# STM32H753_PINOUT.net
KiCad netlist of a schematic drawn in Altium Designer
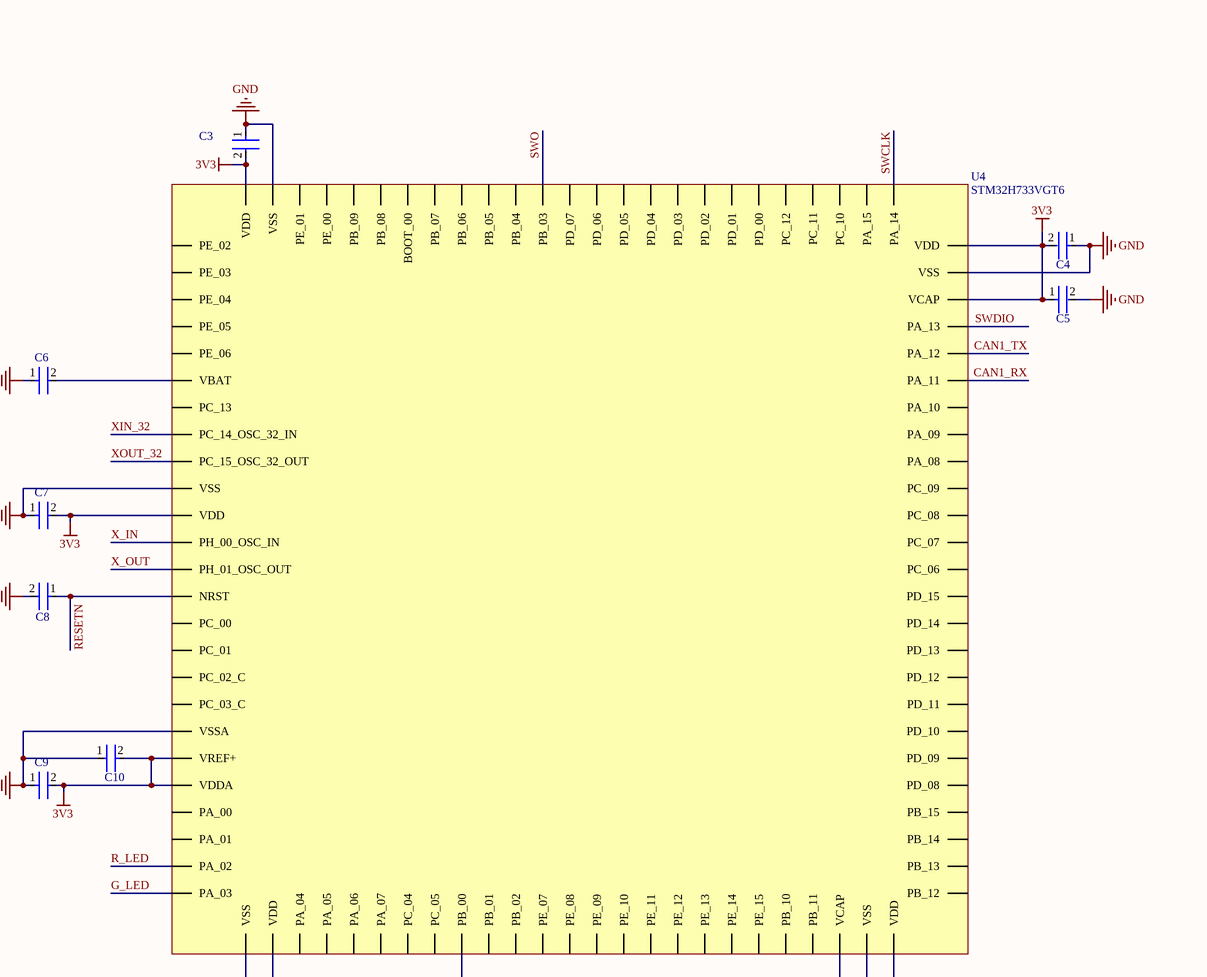
[diagram p0: STM32H753_PINOUT.SchDoc, top middle]
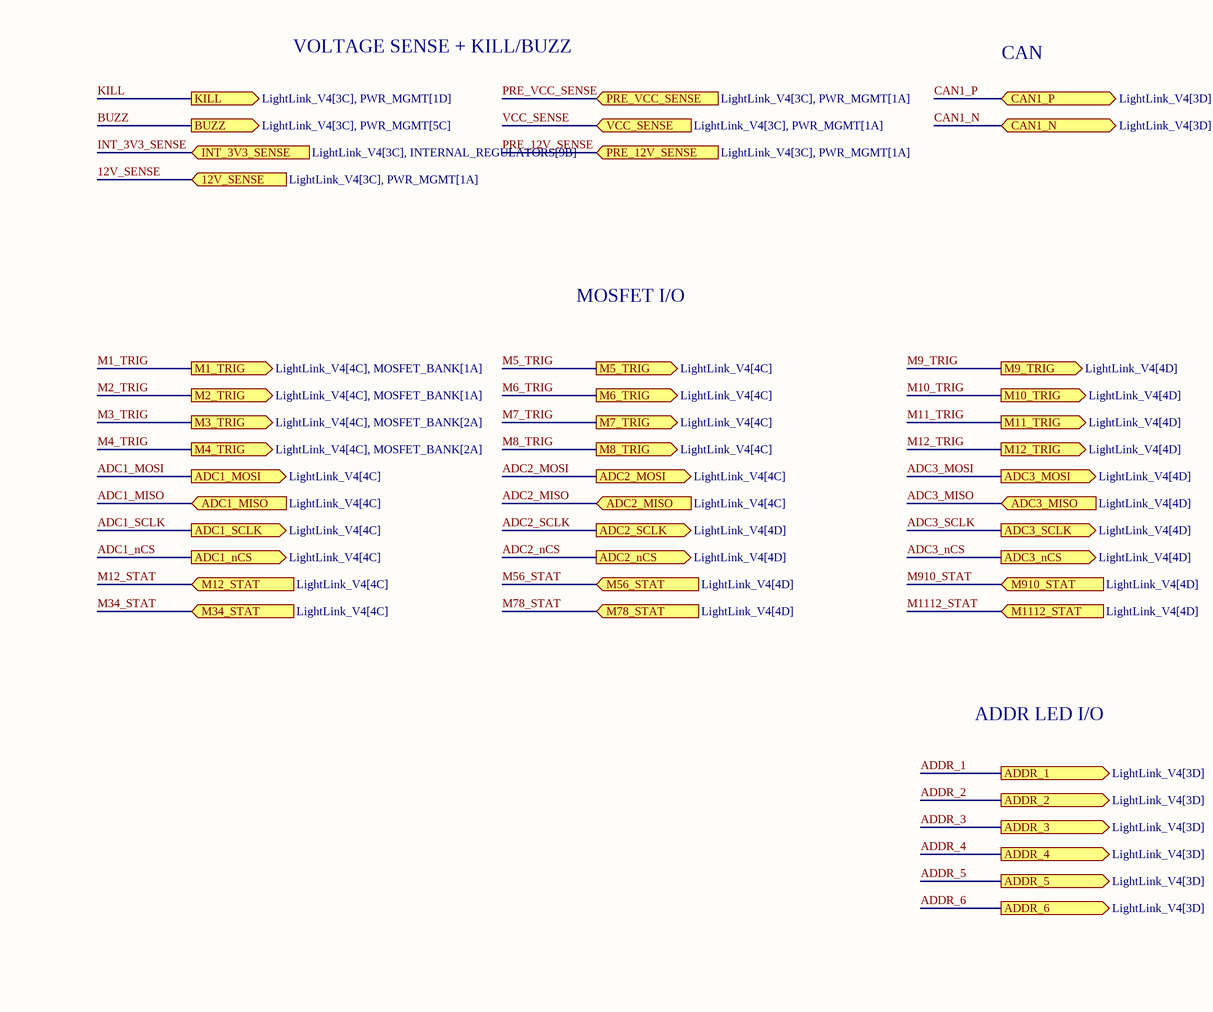
[diagram p1: STM32H753_PINOUT.SchDoc, top right]
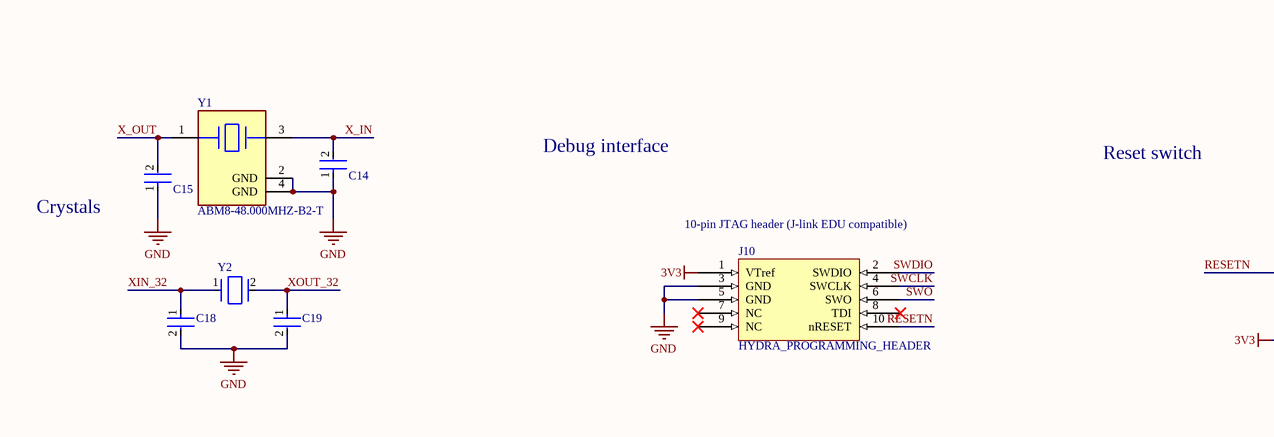
[diagram p2: STM32H753_PINOUT.SchDoc, bottom left]
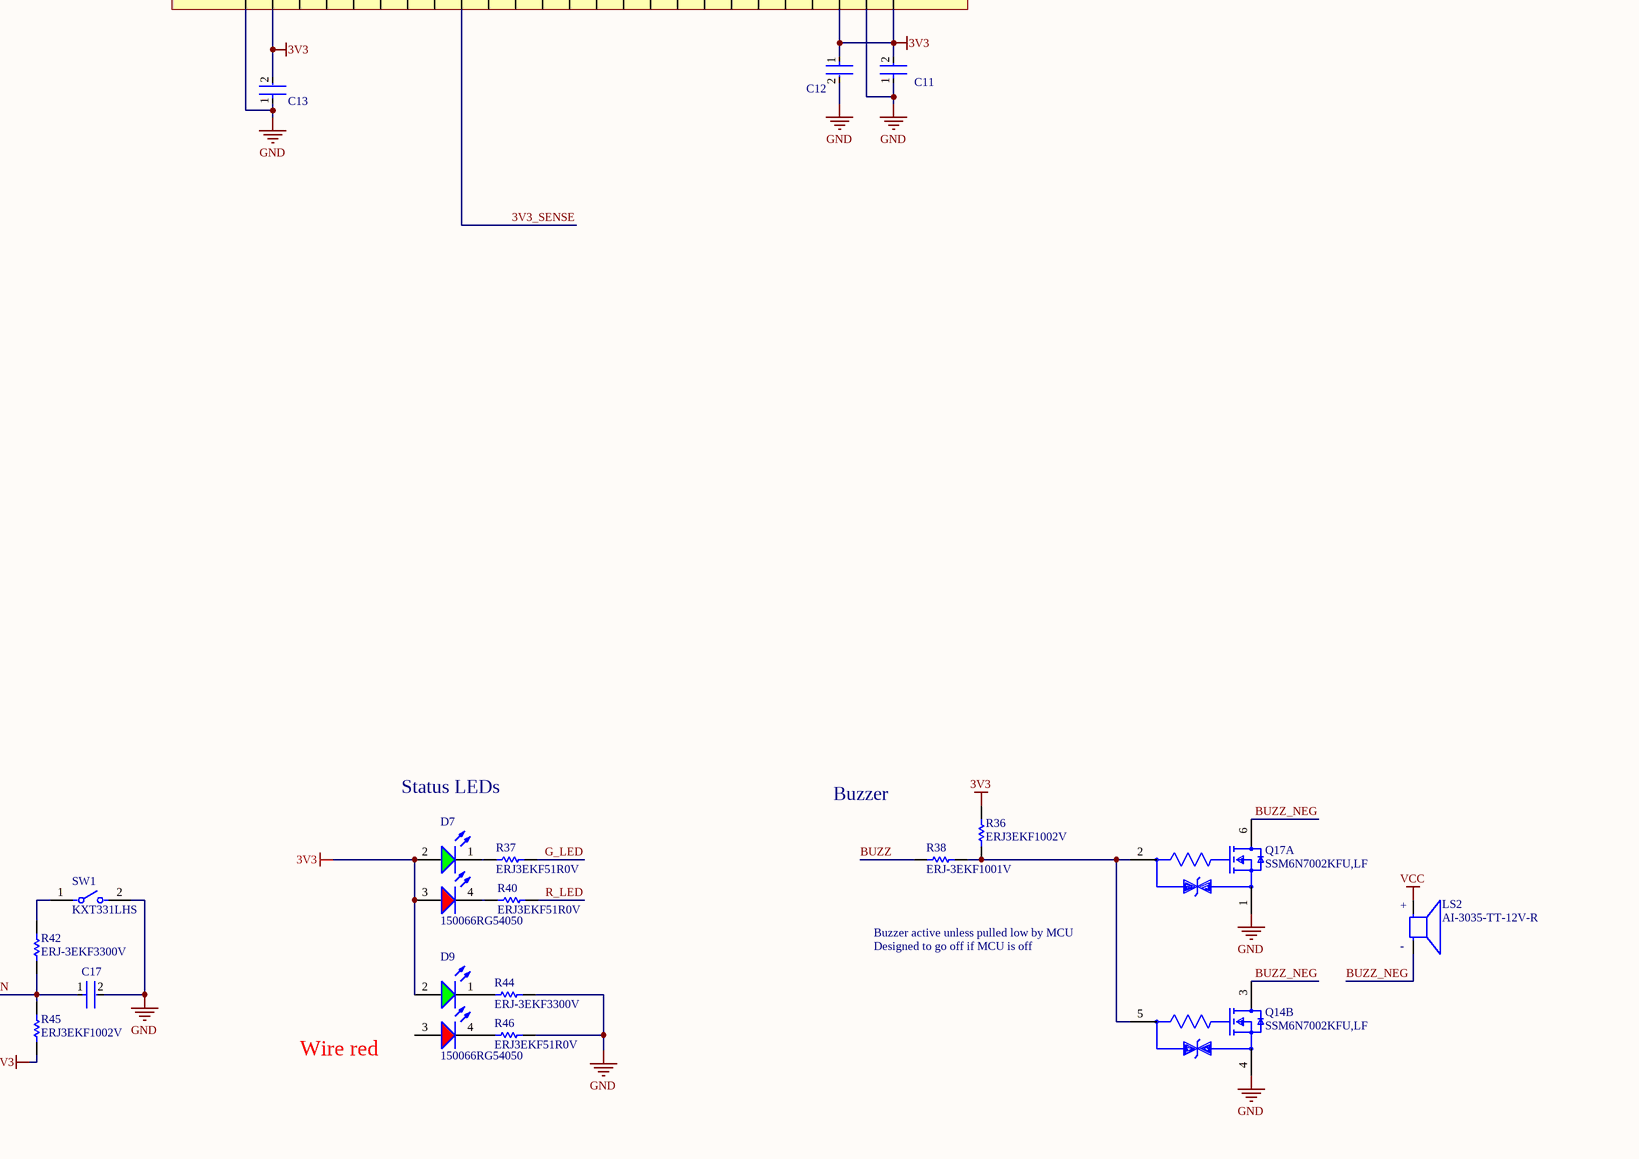
[diagram p3: STM32H753_PINOUT.SchDoc, bottom middle]
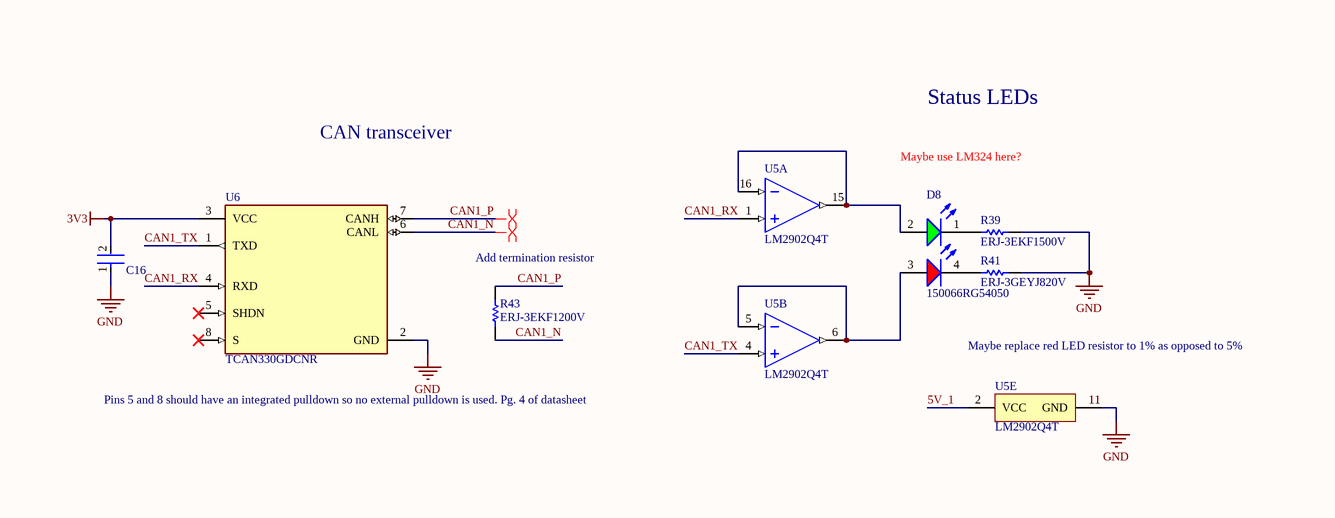
[diagram p4: STM32H753_PINOUT.SchDoc, bottom right]

(export (version "E")
  (design (tool "Eeschema 10.0.6"))
  (components
    (comp (ref "C3")
      (value "C0402C104K8PACTU")
      (footprint "FP-C0402-BB-MFG")
      (fields
        (field (name "MANUFACTURER") "Kemet")
        (field (name "TOLERANCE") "0.1")
        (field (name "OCTOPART") "https://octopart.com/c0402c104k8pactu-kemet-140039")
      )
      (libsource (lib "Altium Content Vault") (part "b4654b650e69147ec39a6b967a45e02"))
    )
    (comp (ref "C4")
      (value "C0402C104K8PACTU")
      (footprint "FP-C0402-BB-MFG")
      (fields
        (field (name "MANUFACTURER") "Kemet")
        (field (name "TOLERANCE") "0.1")
        (field (name "OCTOPART") "https://octopart.com/c0402c104k8pactu-kemet-140039")
      )
      (libsource (lib "Altium Content Vault") (part "b4654b650e69147ec39a6b967a45e02"))
    )
    (comp (ref "C5")
      (value "C1005X7S1A225K050BC")
      (footprint "FP-C1005-050-0_15-0_1-MFG")
      (description "CAP CER 2.2UF 10V X7S 0402")
      (fields (field (name "TOLERANCE") "10%"))
      (libsource (lib "Altium Content Vault") (part "b4654b650e69147ec39a6b967a45e02"))
    )
    (comp (ref "C6")
      (value "C0402C104K8PACTU")
      (footprint "FP-C0402-BB-MFG")
      (fields
        (field (name "MANUFACTURER") "Kemet")
        (field (name "TOLERANCE") "0.1")
        (field (name "OCTOPART") "https://octopart.com/c0402c104k8pactu-kemet-140039")
      )
      (libsource (lib "Altium Content Vault") (part "b4654b650e69147ec39a6b967a45e02"))
    )
    (comp (ref "C7")
      (value "C0402C104K8PACTU")
      (footprint "FP-C0402-BB-MFG")
      (fields
        (field (name "MANUFACTURER") "Kemet")
        (field (name "TOLERANCE") "0.1")
        (field (name "OCTOPART") "https://octopart.com/c0402c104k8pactu-kemet-140039")
      )
      (libsource (lib "Altium Content Vault") (part "b4654b650e69147ec39a6b967a45e02"))
    )
    (comp (ref "C8")
      (value "C0402C104K8PACTU")
      (footprint "FP-C0402-BB-MFG")
      (description "CAP CER 0.1UF 10V X5R 0402")
      (fields (field (name "MANUFACTURER") "Kemet") (field (name "TOLERANCE") "0.1"))
      (libsource (lib "Altium Content Vault") (part "b4654b650e69147ec39a6b967a45e02"))
    )
    (comp (ref "C9")
      (value "C0402C104K8PACTU")
      (footprint "FP-C0402-BB-MFG")
      (fields
        (field (name "MANUFACTURER") "Kemet")
        (field (name "TOLERANCE") "0.1")
        (field (name "OCTOPART") "https://octopart.com/c0402c104k8pactu-kemet-140039")
      )
      (libsource (lib "Altium Content Vault") (part "b4654b650e69147ec39a6b967a45e02"))
    )
    (comp (ref "C10")
      (value "GRM155R71C104KA88D")
      (footprint "FP-GRM15-MFG")
      (description "CAP CER 0.1UF 16V X7R 0402")
      (fields
        (field (name "TOLERANCE") "10%")
        (field (name "OCTOPART") "https://octopart.com/grm155r71c104ka88d-murata-196880")
      )
      (libsource (lib "Altium Content Vault") (part "236180d848d6139a670b325ea6854c9"))
    )
    (comp (ref "C11")
      (value "C0402C104K8PACTU")
      (footprint "FP-C0402-BB-MFG")
      (fields
        (field (name "MANUFACTURER") "Kemet")
        (field (name "TOLERANCE") "0.1")
        (field (name "OCTOPART") "https://octopart.com/c0402c104k8pactu-kemet-140039")
      )
      (libsource (lib "Altium Content Vault") (part "b4654b650e69147ec39a6b967a45e02"))
    )
    (comp (ref "C12")
      (value "C1005X7S1A225K050BC")
      (footprint "FP-C1005-050-0_15-0_1-MFG")
      (description "CAP CER 2.2UF 10V X7S 0402")
      (fields (field (name "TOLERANCE") "10%"))
      (libsource (lib "Altium Content Vault") (part "b4654b650e69147ec39a6b967a45e02"))
    )
    (comp (ref "C13")
      (value "C0402C104K8PACTU")
      (footprint "FP-C0402-BB-MFG")
      (fields
        (field (name "MANUFACTURER") "Kemet")
        (field (name "TOLERANCE") "0.1")
        (field (name "OCTOPART") "https://octopart.com/c0402c104k8pactu-kemet-140039")
      )
      (libsource (lib "Altium Content Vault") (part "b4654b650e69147ec39a6b967a45e02"))
    )
    (comp (ref "C14")
      (value "08051A6R8CAT2A")
      (footprint "FP-0805-L_2_01_0_2-W_1_25-MFG")
      (description "General Purpose Ceramic Capacitor, 0805, 6.8pF, 0.25pF, C0G, 30ppm/°C, 100V")
      (fields (field (name "VOLTAGE") "100V") (field (name "TOLERANCE") "5%"))
      (libsource (lib "Altium Content Vault") (part "02cd4be3c70576c341d710602a673aa"))
    )
    (comp (ref "C15")
      (value "08051A6R8CAT2A")
      (footprint "FP-0805-L_2_01_0_2-W_1_25-MFG")
      (description "General Purpose Ceramic Capacitor, 0805, 6.8pF, 0.25pF, C0G, 30ppm/°C, 100V")
      (fields (field (name "VOLTAGE") "100V") (field (name "TOLERANCE") "5%"))
      (libsource (lib "Altium Content Vault") (part "02cd4be3c70576c341d710602a673aa"))
    )
    (comp (ref "C16")
      (value "C0402C104K8PACTU")
      (footprint "FP-C0402-BB-MFG")
      (description "CAP CER 0.1UF 10V X5R 0402")
      (fields (field (name "MANUFACTURER") "Kemet") (field (name "TOLERANCE") "0.1"))
      (libsource (lib "Altium Content Vault") (part "b4654b650e69147ec39a6b967a45e02"))
    )
    (comp (ref "C17")
      (value "C0402C104K8PACTU")
      (footprint "FP-C0402-BB-MFG")
      (description "CAP CER 0.1UF 10V X5R 0402")
      (fields (field (name "MANUFACTURER") "Kemet") (field (name "TOLERANCE") "0.1"))
      (libsource (lib "Altium Content Vault") (part "b4654b650e69147ec39a6b967a45e02"))
    )
    (comp (ref "C18")
      (value "C0805C180J5GACTU")
      (footprint "FP-C0805C-DN-MFG")
      (description "CAP CER 18PF 50V C0G/NP0 0805")
      (fields
        (field (name "OCTOPART") "https://octopart.com/c0805c180j5gactu-kemet-144810")
        (field (name "TOLERANCE") "0.05")
      )
      (libsource (lib "Altium Content Vault") (part "b4654b650e69147ec39a6b967a45e02"))
    )
    (comp (ref "C19")
      (value "C0805C180J5GACTU")
      (footprint "FP-C0805C-DN-MFG")
      (description "CAP CER 18PF 50V C0G/NP0 0805")
      (fields
        (field (name "OCTOPART") "https://octopart.com/c0805c180j5gactu-kemet-144810")
        (field (name "TOLERANCE") "0.05")
      )
      (libsource (lib "Altium Content Vault") (part "b4654b650e69147ec39a6b967a45e02"))
    )
    (comp (ref "D7")
      (value "150066RG54050")
      (footprint "WL-SBCD_0606")
      (description "Led, Red/Grn, 180Mcd/230Mcd, 624Nm/525Nm Rohs Compliant: Yes")
      (libsource (lib "uORocketry Hardware") (part "WL-SBCD_0606_Red & Green"))
    )
    (comp (ref "D8")
      (value "150066RG54050")
      (footprint "WL-SBCD_0606")
      (description "Led, Red/Grn, 180Mcd/230Mcd, 624Nm/525Nm Rohs Compliant: Yes")
      (libsource (lib "uORocketry Hardware") (part "WL-SBCD_0606_Red & Green"))
    )
    (comp (ref "D9")
      (value "150066RG54050")
      (footprint "WL-SBCD_0606")
      (description "Led, Red/Grn, 180Mcd/230Mcd, 624Nm/525Nm Rohs Compliant: Yes")
      (libsource (lib "uORocketry Hardware") (part "WL-SBCD_0606_Red & Green"))
    )
    (comp (ref "J10")
      (value "HYDRA_PROGRAMMING_HEADER")
      (footprint "3220-10-0300-00-Footprint-1")
      (description "CONN HEADER SMD 10POS 1.27MM (specifically compatible with J-Link EDU cable) PN: 3220-10-0300-00")
      (libsource (lib "uORocketry Hardware") (part "3220-10-0300-00-Symbol-1"))
    )
    (comp (ref "LS2")
      (value "AI-3035-TT-12V-R")
      (footprint "AI-3035-TT-12V-R-Footprint-1")
      (description "Audio Indicator 12V 12mA 110dBA 3.5KHz Resonant Frequency Thru-Hole")
      (libsource (lib "uORocketry Hardware") (part "AI-3035-TT-12V-R"))
    )
    (comp (ref "Q14")
      (value "SSM6N7002KFU,LF")
      (footprint "FP-SSOP6-P-0_65A-MFG")
      (description "MOSFET 2N-CH 60V 0.3A")
      (libsource (lib "Altium Content Vault") (part "088aa6ac103fdeebe0d1c52ece6b7b9"))
    )
    (comp (ref "Q17")
      (value "SSM6N7002KFU,LF")
      (footprint "FP-SSOP6-P-0_65A-MFG")
      (description "MOSFET 2N-CH 60V 0.3A")
      (libsource (lib "Altium Content Vault") (part "088aa6ac103fdeebe0d1c52ece6b7b9"))
    )
    (comp (ref "R36")
      (value "ERJ3EKF1002V")
      (footprint "RESC1609X55X30LL15T15")
      (description "Chip Resistor, 10 KOhm, +/- 1%, 0.1 W, -55 to 155 degC, 0603 (1608 Metric), RoHS, Tape and Reel")
      (fields (field (name "TOLERANCE") "1%") (field (name "MANUFACTURER") "Panasonic"))
      (libsource (lib "Altium Content Vault") (part "RES-2"))
    )
    (comp (ref "R37")
      (value "ERJ3EKF51R0V")
      (footprint "RESC1608X55X30NL15T15")
      (fields (field (name "MANUFACTURER") "Panasonic"))
      (libsource (lib "Altium Content Vault") (part "RES"))
    )
    (comp (ref "R38")
      (value "ERJ-3EKF1001V")
      (footprint "RESC1608X55X30LL15T15")
      (fields (field (name "MANUFACTURER") "Panasonic"))
      (libsource (lib "Altium Content Vault") (part "RES"))
    )
    (comp (ref "R39")
      (value "ERJ-3EKF1500V")
      (footprint "RESC1608X55X30NL15T15")
      (fields (field (name "MANUFACTURER") "Panasonic"))
      (libsource (lib "Altium Content Vault") (part "RES"))
    )
    (comp (ref "R40")
      (value "ERJ3EKF51R0V")
      (footprint "RESC1608X55X30NL15T15")
      (fields (field (name "MANUFACTURER") "Panasonic"))
      (libsource (lib "Altium Content Vault") (part "RES"))
    )
    (comp (ref "R41")
      (value "ERJ-3GEYJ820V")
      (footprint "RESC1608X55X30NL15T15")
      (fields (field (name "MANUFACTURER") "Panasonic"))
      (libsource (lib "Altium Content Vault") (part "RES"))
    )
    (comp (ref "R42")
      (value "ERJ-3EKF3300V")
      (footprint "RESC1608X55X30LL15T15")
      (description "Chip Resistor, 330 Ohm, +/- 1%, 0.1 W, -55 to 155 degC, 0603 (1608 Metric), RoHS, Tape and Reel")
      (libsource (lib "Altium Content Vault") (part "RES-2"))
    )
    (comp (ref "R43")
      (value "ERJ-3EKF1200V")
      (footprint "RESC1609X55X30ML15T15")
      (description "Chip Resistor, 120 Ohm, +/- 1%, 0.1 W, -55 to 155 degC, 0603 (1608 Metric), RoHS, Tape and Reel")
      (fields (field (name "TOLERANCE") "1%") (field (name "MANUFACTURER") "Panasonic"))
      (libsource (lib "Altium Content Vault") (part "RES-2"))
    )
    (comp (ref "R44")
      (value "ERJ-3EKF3300V")
      (footprint "RESC1608X55X30LL15T15")
      (description "Chip Resistor, 330 Ohm, +/- 1%, 0.1 W, -55 to 155 degC, 0603 (1608 Metric), RoHS, Tape and Reel")
      (libsource (lib "Altium Content Vault") (part "RES-2"))
    )
    (comp (ref "R45")
      (value "ERJ3EKF1002V")
      (footprint "RESC1609X55X30LL15T15")
      (description "Chip Resistor, 10 KOhm, +/- 1%, 0.1 W, -55 to 155 degC, 0603 (1608 Metric), RoHS, Tape and Reel")
      (fields (field (name "TOLERANCE") "1%") (field (name "MANUFACTURER") "Panasonic"))
      (libsource (lib "Altium Content Vault") (part "RES-2"))
    )
    (comp (ref "R46")
      (value "ERJ3EKF51R0V")
      (footprint "RESC1608X55X30NL15T15")
      (fields (field (name "MANUFACTURER") "Panasonic"))
      (libsource (lib "Altium Content Vault") (part "RES"))
    )
    (comp (ref "SW1")
      (value "KXT331LHS")
      (footprint "FP-KXT331LHS-MFG")
      (description "SWITCH TACTILE SPST-NO 0.02A 15V")
      (libsource (lib "Altium Content Vault") (part "bb27bde45df87f1f469753f287ef5ae"))
    )
    (comp (ref "U4")
      (value "STM32H733VGT6")
      (footprint "STM32H733VGT6-Footprint-1")
      (description "MCU 32-bit ARM Cortex M7 RISC 1MB Flash 1.8V/2.5V/3.3V 100-Pin LQFP Tray")
      (libsource (lib "uORocketry Hardware") (part "STM32H733VGT6"))
    )
    (comp (ref "U5")
      (value "LM2902Q4T")
      (footprint "LM2902Q4T-Footprint-1")
      (description "LM2902 Series 30 V 1.3 MHz Low-Power Quad Operational Amplifier - QFN-16 (3x3)")
      (libsource (lib "uORocketry Hardware") (part "LM2902Q4T"))
    )
    (comp (ref "U6")
      (value "TCAN330GDCNR")
      (footprint "FP-DCN0008A-MFG")
      (description "IC TRANSCEIVER 1/1 SOT23-8")
      (libsource (lib "Altium Content Vault") (part "22681b49c22ad38c6a4e12e04c36c7a"))
    )
    (comp (ref "Y1")
      (value "ABM8-48.000MHZ-B2-T")
      (footprint "FP-ABM8-MFG")
      (description "Crystal 48MHz ±20ppm 18pF SMD-4 3.2mm x 2.5mm")
      (fields (field (name "TOLERANCE") "20ppm"))
      (libsource (lib "Altium Content Vault") (part "dfdb7f9a12507849fb681da9a70121c"))
    )
    (comp (ref "Y2")
      (value "ECS-.327-12.5-1210-TR")
      (footprint "FP-ECX-1210-MFG")
      (description "CRYSTAL 32.7680KHZ 12.5PF SMD")
      (fields
        (field (name "OCTOPART") "https://octopart.com/ecs-.327-12.5-1210-tr-ecs+international-81221340")
        (field (name "TOLERANCE") "20ppm")
      )
      (libsource (lib "Altium Content Vault") (part "99724985039315a44fd0d1401b84e49"))
    )
  )
  (nets
    (net (code "1") (name "/3V3_SENSE") (class "Default")
      (node (ref "U4") (pin "34") (pinfunction "PB_00_34") (pintype "passive"))
    )
    (net (code "2") (name "/5V_1") (class "Default")
      (node (ref "U5") (pin "2") (pinfunction "VCC_2") (pintype "power_in"))
    )
    (net (code "22") (name "/BUZZ") (class "Default")
      (node (ref "R38") (pin "1") (pinfunction "1_1") (pintype "passive"))
    )
    (net (code "23") (name "/BUZZ_NEG") (class "Default")
      (node (ref "LS2") (pin "N") (pinfunction "N_N") (pintype "passive"))
      (node (ref "Q14") (pin "3") (pinfunction "Drain2_3") (pintype "passive"))
      (node (ref "Q17") (pin "6") (pinfunction "Drain1_6") (pintype "passive"))
    )
    (net (code "24") (name "/CAN1_N") (class "Default")
      (node (ref "R43") (pin "1") (pinfunction "1_1") (pintype "passive"))
      (node (ref "U6") (pin "6") (pinfunction "CANL_6") (pintype "bidirectional"))
    )
    (net (code "25") (name "/CAN1_P") (class "Default")
      (node (ref "R43") (pin "2") (pinfunction "2_2") (pintype "passive"))
      (node (ref "U6") (pin "7") (pinfunction "CANH_7") (pintype "bidirectional"))
    )
    (net (code "26") (name "/CAN1_RX") (class "Default")
      (node (ref "U4") (pin "70") (pinfunction "PA_11_70") (pintype "passive"))
      (node (ref "U5") (pin "1") (pinfunction "1IN+_1") (pintype "input"))
      (node (ref "U6") (pin "4") (pinfunction "RXD_4") (pintype "input"))
    )
    (net (code "27") (name "/CAN1_TX") (class "Default")
      (node (ref "U4") (pin "71") (pinfunction "PA_12_71") (pintype "passive"))
      (node (ref "U5") (pin "4") (pinfunction "2IN+_4") (pintype "input"))
      (node (ref "U6") (pin "1") (pinfunction "TXD_1") (pintype "output"))
    )
    (net (code "28") (name "/G_LED") (class "Default")
      (node (ref "R37") (pin "2") (pinfunction "2_2") (pintype "passive"))
      (node (ref "U4") (pin "25") (pinfunction "PA_03_25") (pintype "passive"))
    )
    (net (code "51") (name "/RESETN") (class "Default")
      (node (ref "C17") (pin "1") (pinfunction "1_1") (pintype "passive"))
      (node (ref "C8") (pin "1") (pinfunction "1_1") (pintype "passive"))
      (node (ref "J10") (pin "10") (pinfunction "nRESET_10") (pintype "input"))
      (node (ref "R42") (pin "1") (pinfunction "1_1") (pintype "passive"))
      (node (ref "R45") (pin "2") (pinfunction "2_2") (pintype "passive"))
      (node (ref "U4") (pin "14") (pinfunction "NRST_14") (pintype "passive"))
    )
    (net (code "52") (name "/R_LED") (class "Default")
      (node (ref "R40") (pin "2") (pinfunction "2_2") (pintype "passive"))
      (node (ref "U4") (pin "24") (pinfunction "PA_02_24") (pintype "passive"))
    )
    (net (code "53") (name "/SWCLK") (class "Default")
      (node (ref "J10") (pin "4") (pinfunction "SWCLK_4") (pintype "input"))
      (node (ref "U4") (pin "76") (pinfunction "PA_14_76") (pintype "passive"))
    )
    (net (code "54") (name "/SWDIO") (class "Default")
      (node (ref "J10") (pin "2") (pinfunction "SWDIO_2") (pintype "input"))
      (node (ref "U4") (pin "72") (pinfunction "PA_13_72") (pintype "passive"))
    )
    (net (code "55") (name "/SWO") (class "Default")
      (node (ref "J10") (pin "6") (pinfunction "SWO_6") (pintype "input"))
      (node (ref "U4") (pin "89") (pinfunction "PB_03_89") (pintype "passive"))
    )
    (net (code "57") (name "/XIN_32") (class "Default")
      (node (ref "C18") (pin "1") (pinfunction "1_1") (pintype "passive"))
      (node (ref "U4") (pin "8") (pinfunction "PC_14_OSC_32_IN_8") (pintype "passive"))
      (node (ref "Y2") (pin "1") (pinfunction "In/Out_1") (pintype "passive"))
    )
    (net (code "58") (name "/XOUT_32") (class "Default")
      (node (ref "C19") (pin "1") (pinfunction "1_1") (pintype "passive"))
      (node (ref "U4") (pin "9") (pinfunction "PC_15_OSC_32_OUT_9") (pintype "passive"))
      (node (ref "Y2") (pin "2") (pinfunction "Out/In_2") (pintype "passive"))
    )
    (net (code "59") (name "/X_IN") (class "Default")
      (node (ref "C14") (pin "2") (pinfunction "2_2") (pintype "passive"))
      (node (ref "U4") (pin "12") (pinfunction "PH_00_OSC_IN_12") (pintype "passive"))
      (node (ref "Y1") (pin "3") (pinfunction "3_3") (pintype "passive"))
    )
    (net (code "60") (name "/X_OUT") (class "Default")
      (node (ref "C15") (pin "2") (pinfunction "2_2") (pintype "passive"))
      (node (ref "U4") (pin "13") (pinfunction "PH_01_OSC_OUT_13") (pintype "passive"))
      (node (ref "Y1") (pin "1") (pinfunction "1_1") (pintype "passive"))
    )
    (net (code "61") (name "3V3") (class "Default")
      (node (ref "C10") (pin "2") (pinfunction "2_2") (pintype "passive"))
      (node (ref "C11") (pin "2") (pinfunction "2_2") (pintype "passive"))
      (node (ref "C12") (pin "1") (pinfunction "1_1") (pintype "passive"))
      (node (ref "C13") (pin "2") (pinfunction "2_2") (pintype "passive"))
      (node (ref "C16") (pin "2") (pinfunction "2_2") (pintype "passive"))
      (node (ref "C3") (pin "2") (pinfunction "2_2") (pintype "passive"))
      (node (ref "C4") (pin "2") (pinfunction "2_2") (pintype "passive"))
      (node (ref "C5") (pin "1") (pinfunction "1_1") (pintype "passive"))
      (node (ref "C7") (pin "2") (pinfunction "2_2") (pintype "passive"))
      (node (ref "C9") (pin "2") (pinfunction "2_2") (pintype "passive"))
      (node (ref "D7") (pin "2") (pinfunction "A_2") (pintype "passive"))
      (node (ref "D7") (pin "3") (pinfunction "A_3") (pintype "passive"))
      (node (ref "D9") (pin "2") (pinfunction "A_2") (pintype "passive"))
      (node (ref "J10") (pin "1") (pinfunction "VTref_1") (pintype "input"))
      (node (ref "R36") (pin "2") (pinfunction "2_2") (pintype "passive"))
      (node (ref "R45") (pin "1") (pinfunction "1_1") (pintype "passive"))
      (node (ref "U4") (pin "100") (pinfunction "VDD_100") (pintype "passive"))
      (node (ref "U4") (pin "11") (pinfunction "VDD_11") (pintype "passive"))
      (node (ref "U4") (pin "20") (pinfunction "VREF+_20") (pintype "passive"))
      (node (ref "U4") (pin "21") (pinfunction "VDDA_21") (pintype "passive"))
      (node (ref "U4") (pin "27") (pinfunction "VDD_27") (pintype "passive"))
      (node (ref "U4") (pin "48") (pinfunction "VCAP_48") (pintype "passive"))
      (node (ref "U4") (pin "50") (pinfunction "VDD_50") (pintype "passive"))
      (node (ref "U4") (pin "73") (pinfunction "VCAP_73") (pintype "passive"))
      (node (ref "U4") (pin "75") (pinfunction "VDD_75") (pintype "passive"))
      (node (ref "U6") (pin "3") (pinfunction "VCC_3") (pintype "power_in"))
    )
    (net (code "62") (name "GND") (class "Default")
      (node (ref "C10") (pin "1") (pinfunction "1_1") (pintype "passive"))
      (node (ref "C11") (pin "1") (pinfunction "1_1") (pintype "passive"))
      (node (ref "C12") (pin "2") (pinfunction "2_2") (pintype "passive"))
      (node (ref "C13") (pin "1") (pinfunction "1_1") (pintype "passive"))
      (node (ref "C14") (pin "1") (pinfunction "1_1") (pintype "passive"))
      (node (ref "C15") (pin "1") (pinfunction "1_1") (pintype "passive"))
      (node (ref "C16") (pin "1") (pinfunction "1_1") (pintype "passive"))
      (node (ref "C17") (pin "2") (pinfunction "2_2") (pintype "passive"))
      (node (ref "C18") (pin "2") (pinfunction "2_2") (pintype "passive"))
      (node (ref "C19") (pin "2") (pinfunction "2_2") (pintype "passive"))
      (node (ref "C3") (pin "1") (pinfunction "1_1") (pintype "passive"))
      (node (ref "C4") (pin "1") (pinfunction "1_1") (pintype "passive"))
      (node (ref "C5") (pin "2") (pinfunction "2_2") (pintype "passive"))
      (node (ref "C6") (pin "1") (pinfunction "1_1") (pintype "passive"))
      (node (ref "C7") (pin "1") (pinfunction "1_1") (pintype "passive"))
      (node (ref "C8") (pin "2") (pinfunction "2_2") (pintype "passive"))
      (node (ref "C9") (pin "1") (pinfunction "1_1") (pintype "passive"))
      (node (ref "J10") (pin "3") (pinfunction "GND_3") (pintype "input"))
      (node (ref "J10") (pin "5") (pinfunction "GND_5") (pintype "input"))
      (node (ref "Q14") (pin "4") (pinfunction "Source2_4") (pintype "passive"))
      (node (ref "Q17") (pin "1") (pinfunction "Source1_1") (pintype "passive"))
      (node (ref "R39") (pin "2") (pinfunction "2_2") (pintype "passive"))
      (node (ref "R41") (pin "2") (pinfunction "2_2") (pintype "passive"))
      (node (ref "R44") (pin "2") (pinfunction "2_2") (pintype "passive"))
      (node (ref "R46") (pin "2") (pinfunction "2_2") (pintype "passive"))
      (node (ref "SW1") (pin "2") (pinfunction "2_2") (pintype "passive"))
      (node (ref "U4") (pin "10") (pinfunction "VSS_10") (pintype "passive"))
      (node (ref "U4") (pin "19") (pinfunction "VSSA_19") (pintype "passive"))
      (node (ref "U4") (pin "26") (pinfunction "VSS_26") (pintype "passive"))
      (node (ref "U4") (pin "49") (pinfunction "VSS_49") (pintype "passive"))
      (node (ref "U4") (pin "74") (pinfunction "VSS_74") (pintype "passive"))
      (node (ref "U4") (pin "99") (pinfunction "VSS_99") (pintype "passive"))
      (node (ref "U5") (pin "11") (pinfunction "GND_11") (pintype "power_in"))
      (node (ref "U6") (pin "2") (pinfunction "GND_2") (pintype "power_in"))
      (node (ref "Y1") (pin "2") (pinfunction "GND_2") (pintype "power_in"))
      (node (ref "Y1") (pin "4") (pinfunction "GND_4") (pintype "power_in"))
    )
    (net (code "63") (name "Net-(D7-K-Pad1)") (class "Default")
      (node (ref "D7") (pin "1") (pinfunction "K_1") (pintype "passive"))
      (node (ref "R37") (pin "1") (pinfunction "1_1") (pintype "passive"))
    )
    (net (code "64") (name "Net-(D7-K-Pad4)") (class "Default")
      (node (ref "D7") (pin "4") (pinfunction "K_4") (pintype "passive"))
      (node (ref "R40") (pin "1") (pinfunction "1_1") (pintype "passive"))
    )
    (net (code "65") (name "Net-(D8-K-Pad1)") (class "Default")
      (node (ref "D8") (pin "1") (pinfunction "K_1") (pintype "passive"))
      (node (ref "R39") (pin "1") (pinfunction "1_1") (pintype "passive"))
    )
    (net (code "66") (name "Net-(D8-K-Pad4)") (class "Default")
      (node (ref "D8") (pin "4") (pinfunction "K_4") (pintype "passive"))
      (node (ref "R41") (pin "1") (pinfunction "1_1") (pintype "passive"))
    )
    (net (code "67") (name "Net-(D9-K-Pad1)") (class "Default")
      (node (ref "D9") (pin "1") (pinfunction "K_1") (pintype "passive"))
      (node (ref "R44") (pin "1") (pinfunction "1_1") (pintype "passive"))
    )
    (net (code "68") (name "Net-(D9-K-Pad4)") (class "Default")
      (node (ref "D9") (pin "4") (pinfunction "K_4") (pintype "passive"))
      (node (ref "R46") (pin "1") (pinfunction "1_1") (pintype "passive"))
    )
    (net (code "69") (name "Net-(Q14B-Gate2)") (class "Default")
      (node (ref "Q14") (pin "5") (pinfunction "Gate2_5") (pintype "passive"))
      (node (ref "Q17") (pin "2") (pinfunction "Gate1_2") (pintype "passive"))
      (node (ref "R36") (pin "1") (pinfunction "1_1") (pintype "passive"))
      (node (ref "R38") (pin "2") (pinfunction "2_2") (pintype "passive"))
    )
    (net (code "70") (name "Net-(R42-Pad2)") (class "Default")
      (node (ref "R42") (pin "2") (pinfunction "2_2") (pintype "passive"))
      (node (ref "SW1") (pin "1") (pinfunction "1_1") (pintype "passive"))
    )
    (net (code "71") (name "Net-(U4-VBAT)") (class "Default")
      (node (ref "C6") (pin "2") (pinfunction "2_2") (pintype "passive"))
      (node (ref "U4") (pin "6") (pinfunction "VBAT_6") (pintype "passive"))
    )
    (net (code "72") (name "Net-(U5A-1IN-)") (class "Default")
      (node (ref "D8") (pin "2") (pinfunction "A_2") (pintype "passive"))
      (node (ref "U5") (pin "15") (pinfunction "1OUT_15") (pintype "output"))
      (node (ref "U5") (pin "16") (pinfunction "1IN-_16") (pintype "input"))
    )
    (net (code "73") (name "Net-(U5B-2IN-)") (class "Default")
      (node (ref "D8") (pin "3") (pinfunction "A_3") (pintype "passive"))
      (node (ref "U5") (pin "5") (pinfunction "2IN-_5") (pintype "input"))
      (node (ref "U5") (pin "6") (pinfunction "2OUT_6") (pintype "output"))
    )
    (net (code "74") (name "VCC") (class "Default")
      (node (ref "LS2") (pin "P") (pinfunction "P_P") (pintype "passive"))
    )
    (net (code "75") (name "unconnected-(D9-A-Pad3)") (class "Default")
      (node (ref "D9") (pin "3") (pinfunction "A_3") (pintype "passive"))
    )
    (net (code "76") (name "unconnected-(J10-NC-Pad7)") (class "Default")
      (node (ref "J10") (pin "7") (pinfunction "NC_7") (pintype "input+no_connect"))
    )
    (net (code "77") (name "unconnected-(J10-NC-Pad9)") (class "Default")
      (node (ref "J10") (pin "9") (pinfunction "NC_9") (pintype "input+no_connect"))
    )
    (net (code "78") (name "unconnected-(J10-TDI-Pad8)") (class "Default")
      (node (ref "J10") (pin "8") (pinfunction "TDI_8") (pintype "input+no_connect"))
    )
    (net (code "79") (name "unconnected-(U4-BOOT_00-Pad94)") (class "Default")
      (node (ref "U4") (pin "94") (pinfunction "BOOT_00_94") (pintype "passive"))
    )
    (net (code "80") (name "unconnected-(U4-PA_00-Pad22)") (class "Default")
      (node (ref "U4") (pin "22") (pinfunction "PA_00_22") (pintype "passive"))
    )
    (net (code "81") (name "unconnected-(U4-PA_01-Pad23)") (class "Default")
      (node (ref "U4") (pin "23") (pinfunction "PA_01_23") (pintype "passive"))
    )
    (net (code "82") (name "unconnected-(U4-PA_04-Pad28)") (class "Default")
      (node (ref "U4") (pin "28") (pinfunction "PA_04_28") (pintype "passive"))
    )
    (net (code "83") (name "unconnected-(U4-PA_05-Pad29)") (class "Default")
      (node (ref "U4") (pin "29") (pinfunction "PA_05_29") (pintype "passive"))
    )
    (net (code "84") (name "unconnected-(U4-PA_06-Pad30)") (class "Default")
      (node (ref "U4") (pin "30") (pinfunction "PA_06_30") (pintype "passive"))
    )
    (net (code "85") (name "unconnected-(U4-PA_07-Pad31)") (class "Default")
      (node (ref "U4") (pin "31") (pinfunction "PA_07_31") (pintype "passive"))
    )
    (net (code "86") (name "unconnected-(U4-PA_08-Pad67)") (class "Default")
      (node (ref "U4") (pin "67") (pinfunction "PA_08_67") (pintype "passive"))
    )
    (net (code "87") (name "unconnected-(U4-PA_09-Pad68)") (class "Default")
      (node (ref "U4") (pin "68") (pinfunction "PA_09_68") (pintype "passive"))
    )
    (net (code "88") (name "unconnected-(U4-PA_10-Pad69)") (class "Default")
      (node (ref "U4") (pin "69") (pinfunction "PA_10_69") (pintype "passive"))
    )
    (net (code "89") (name "unconnected-(U4-PA_15-Pad77)") (class "Default")
      (node (ref "U4") (pin "77") (pinfunction "PA_15_77") (pintype "passive"))
    )
    (net (code "90") (name "unconnected-(U4-PB_01-Pad35)") (class "Default")
      (node (ref "U4") (pin "35") (pinfunction "PB_01_35") (pintype "passive"))
    )
    (net (code "91") (name "unconnected-(U4-PB_02-Pad36)") (class "Default")
      (node (ref "U4") (pin "36") (pinfunction "PB_02_36") (pintype "passive"))
    )
    (net (code "92") (name "unconnected-(U4-PB_04-Pad90)") (class "Default")
      (node (ref "U4") (pin "90") (pinfunction "PB_04_90") (pintype "passive"))
    )
    (net (code "93") (name "unconnected-(U4-PB_05-Pad91)") (class "Default")
      (node (ref "U4") (pin "91") (pinfunction "PB_05_91") (pintype "passive"))
    )
    (net (code "94") (name "unconnected-(U4-PB_06-Pad92)") (class "Default")
      (node (ref "U4") (pin "92") (pinfunction "PB_06_92") (pintype "passive"))
    )
    (net (code "95") (name "unconnected-(U4-PB_07-Pad93)") (class "Default")
      (node (ref "U4") (pin "93") (pinfunction "PB_07_93") (pintype "passive"))
    )
    (net (code "96") (name "unconnected-(U4-PB_08-Pad95)") (class "Default")
      (node (ref "U4") (pin "95") (pinfunction "PB_08_95") (pintype "passive"))
    )
    (net (code "97") (name "unconnected-(U4-PB_09-Pad96)") (class "Default")
      (node (ref "U4") (pin "96") (pinfunction "PB_09_96") (pintype "passive"))
    )
    (net (code "98") (name "unconnected-(U4-PB_10-Pad46)") (class "Default")
      (node (ref "U4") (pin "46") (pinfunction "PB_10_46") (pintype "passive"))
    )
    (net (code "99") (name "unconnected-(U4-PB_11-Pad47)") (class "Default")
      (node (ref "U4") (pin "47") (pinfunction "PB_11_47") (pintype "passive"))
    )
    (net (code "100") (name "unconnected-(U4-PB_12-Pad51)") (class "Default")
      (node (ref "U4") (pin "51") (pinfunction "PB_12_51") (pintype "passive"))
    )
    (net (code "101") (name "unconnected-(U4-PB_13-Pad52)") (class "Default")
      (node (ref "U4") (pin "52") (pinfunction "PB_13_52") (pintype "passive"))
    )
    (net (code "102") (name "unconnected-(U4-PB_14-Pad53)") (class "Default")
      (node (ref "U4") (pin "53") (pinfunction "PB_14_53") (pintype "passive"))
    )
    (net (code "103") (name "unconnected-(U4-PB_15-Pad54)") (class "Default")
      (node (ref "U4") (pin "54") (pinfunction "PB_15_54") (pintype "passive"))
    )
    (net (code "104") (name "unconnected-(U4-PC_00-Pad15)") (class "Default")
      (node (ref "U4") (pin "15") (pinfunction "PC_00_15") (pintype "passive"))
    )
    (net (code "105") (name "unconnected-(U4-PC_01-Pad16)") (class "Default")
      (node (ref "U4") (pin "16") (pinfunction "PC_01_16") (pintype "passive"))
    )
    (net (code "106") (name "unconnected-(U4-PC_02_C-Pad17)") (class "Default")
      (node (ref "U4") (pin "17") (pinfunction "PC_02_C_17") (pintype "passive"))
    )
    (net (code "107") (name "unconnected-(U4-PC_03_C-Pad18)") (class "Default")
      (node (ref "U4") (pin "18") (pinfunction "PC_03_C_18") (pintype "passive"))
    )
    (net (code "108") (name "unconnected-(U4-PC_04-Pad32)") (class "Default")
      (node (ref "U4") (pin "32") (pinfunction "PC_04_32") (pintype "passive"))
    )
    (net (code "109") (name "unconnected-(U4-PC_05-Pad33)") (class "Default")
      (node (ref "U4") (pin "33") (pinfunction "PC_05_33") (pintype "passive"))
    )
    (net (code "110") (name "unconnected-(U4-PC_06-Pad63)") (class "Default")
      (node (ref "U4") (pin "63") (pinfunction "PC_06_63") (pintype "passive"))
    )
    (net (code "111") (name "unconnected-(U4-PC_07-Pad64)") (class "Default")
      (node (ref "U4") (pin "64") (pinfunction "PC_07_64") (pintype "passive"))
    )
    (net (code "112") (name "unconnected-(U4-PC_08-Pad65)") (class "Default")
      (node (ref "U4") (pin "65") (pinfunction "PC_08_65") (pintype "passive"))
    )
    (net (code "113") (name "unconnected-(U4-PC_09-Pad66)") (class "Default")
      (node (ref "U4") (pin "66") (pinfunction "PC_09_66") (pintype "passive"))
    )
    (net (code "114") (name "unconnected-(U4-PC_10-Pad78)") (class "Default")
      (node (ref "U4") (pin "78") (pinfunction "PC_10_78") (pintype "passive"))
    )
    (net (code "115") (name "unconnected-(U4-PC_11-Pad79)") (class "Default")
      (node (ref "U4") (pin "79") (pinfunction "PC_11_79") (pintype "passive"))
    )
    (net (code "116") (name "unconnected-(U4-PC_12-Pad80)") (class "Default")
      (node (ref "U4") (pin "80") (pinfunction "PC_12_80") (pintype "passive"))
    )
    (net (code "117") (name "unconnected-(U4-PC_13-Pad7)") (class "Default")
      (node (ref "U4") (pin "7") (pinfunction "PC_13_7") (pintype "passive"))
    )
    (net (code "118") (name "unconnected-(U4-PD_00-Pad81)") (class "Default")
      (node (ref "U4") (pin "81") (pinfunction "PD_00_81") (pintype "passive"))
    )
    (net (code "119") (name "unconnected-(U4-PD_01-Pad82)") (class "Default")
      (node (ref "U4") (pin "82") (pinfunction "PD_01_82") (pintype "passive"))
    )
    (net (code "120") (name "unconnected-(U4-PD_02-Pad83)") (class "Default")
      (node (ref "U4") (pin "83") (pinfunction "PD_02_83") (pintype "passive"))
    )
    (net (code "121") (name "unconnected-(U4-PD_03-Pad84)") (class "Default")
      (node (ref "U4") (pin "84") (pinfunction "PD_03_84") (pintype "passive"))
    )
    (net (code "122") (name "unconnected-(U4-PD_04-Pad85)") (class "Default")
      (node (ref "U4") (pin "85") (pinfunction "PD_04_85") (pintype "passive"))
    )
    (net (code "123") (name "unconnected-(U4-PD_05-Pad86)") (class "Default")
      (node (ref "U4") (pin "86") (pinfunction "PD_05_86") (pintype "passive"))
    )
    (net (code "124") (name "unconnected-(U4-PD_06-Pad87)") (class "Default")
      (node (ref "U4") (pin "87") (pinfunction "PD_06_87") (pintype "passive"))
    )
    (net (code "125") (name "unconnected-(U4-PD_07-Pad88)") (class "Default")
      (node (ref "U4") (pin "88") (pinfunction "PD_07_88") (pintype "passive"))
    )
    (net (code "126") (name "unconnected-(U4-PD_08-Pad55)") (class "Default")
      (node (ref "U4") (pin "55") (pinfunction "PD_08_55") (pintype "passive"))
    )
    (net (code "127") (name "unconnected-(U4-PD_09-Pad56)") (class "Default")
      (node (ref "U4") (pin "56") (pinfunction "PD_09_56") (pintype "passive"))
    )
    (net (code "128") (name "unconnected-(U4-PD_10-Pad57)") (class "Default")
      (node (ref "U4") (pin "57") (pinfunction "PD_10_57") (pintype "passive"))
    )
    (net (code "129") (name "unconnected-(U4-PD_11-Pad58)") (class "Default")
      (node (ref "U4") (pin "58") (pinfunction "PD_11_58") (pintype "passive"))
    )
    (net (code "130") (name "unconnected-(U4-PD_12-Pad59)") (class "Default")
      (node (ref "U4") (pin "59") (pinfunction "PD_12_59") (pintype "passive"))
    )
    (net (code "131") (name "unconnected-(U4-PD_13-Pad60)") (class "Default")
      (node (ref "U4") (pin "60") (pinfunction "PD_13_60") (pintype "passive"))
    )
    (net (code "132") (name "unconnected-(U4-PD_14-Pad61)") (class "Default")
      (node (ref "U4") (pin "61") (pinfunction "PD_14_61") (pintype "passive"))
    )
    (net (code "133") (name "unconnected-(U4-PD_15-Pad62)") (class "Default")
      (node (ref "U4") (pin "62") (pinfunction "PD_15_62") (pintype "passive"))
    )
    (net (code "134") (name "unconnected-(U4-PE_00-Pad97)") (class "Default")
      (node (ref "U4") (pin "97") (pinfunction "PE_00_97") (pintype "passive"))
    )
    (net (code "135") (name "unconnected-(U4-PE_01-Pad98)") (class "Default")
      (node (ref "U4") (pin "98") (pinfunction "PE_01_98") (pintype "passive"))
    )
    (net (code "136") (name "unconnected-(U4-PE_02-Pad1)") (class "Default")
      (node (ref "U4") (pin "1") (pinfunction "PE_02_1") (pintype "passive"))
    )
    (net (code "137") (name "unconnected-(U4-PE_03-Pad2)") (class "Default")
      (node (ref "U4") (pin "2") (pinfunction "PE_03_2") (pintype "passive"))
    )
    (net (code "138") (name "unconnected-(U4-PE_04-Pad3)") (class "Default")
      (node (ref "U4") (pin "3") (pinfunction "PE_04_3") (pintype "passive"))
    )
    (net (code "139") (name "unconnected-(U4-PE_05-Pad4)") (class "Default")
      (node (ref "U4") (pin "4") (pinfunction "PE_05_4") (pintype "passive"))
    )
    (net (code "140") (name "unconnected-(U4-PE_06-Pad5)") (class "Default")
      (node (ref "U4") (pin "5") (pinfunction "PE_06_5") (pintype "passive"))
    )
    (net (code "141") (name "unconnected-(U4-PE_07-Pad37)") (class "Default")
      (node (ref "U4") (pin "37") (pinfunction "PE_07_37") (pintype "passive"))
    )
    (net (code "142") (name "unconnected-(U4-PE_08-Pad38)") (class "Default")
      (node (ref "U4") (pin "38") (pinfunction "PE_08_38") (pintype "passive"))
    )
    (net (code "143") (name "unconnected-(U4-PE_09-Pad39)") (class "Default")
      (node (ref "U4") (pin "39") (pinfunction "PE_09_39") (pintype "passive"))
    )
    (net (code "144") (name "unconnected-(U4-PE_10-Pad40)") (class "Default")
      (node (ref "U4") (pin "40") (pinfunction "PE_10_40") (pintype "passive"))
    )
    (net (code "145") (name "unconnected-(U4-PE_11-Pad41)") (class "Default")
      (node (ref "U4") (pin "41") (pinfunction "PE_11_41") (pintype "passive"))
    )
    (net (code "146") (name "unconnected-(U4-PE_12-Pad42)") (class "Default")
      (node (ref "U4") (pin "42") (pinfunction "PE_12_42") (pintype "passive"))
    )
    (net (code "147") (name "unconnected-(U4-PE_13-Pad43)") (class "Default")
      (node (ref "U4") (pin "43") (pinfunction "PE_13_43") (pintype "passive"))
    )
    (net (code "148") (name "unconnected-(U4-PE_14-Pad44)") (class "Default")
      (node (ref "U4") (pin "44") (pinfunction "PE_14_44") (pintype "passive"))
    )
    (net (code "149") (name "unconnected-(U4-PE_15-Pad45)") (class "Default")
      (node (ref "U4") (pin "45") (pinfunction "PE_15_45") (pintype "passive"))
    )
    (net (code "150") (name "unconnected-(U6-S-Pad8)") (class "Default")
      (node (ref "U6") (pin "8") (pinfunction "S_8") (pintype "input+no_connect"))
    )
    (net (code "151") (name "unconnected-(U6-SHDN-Pad5)") (class "Default")
      (node (ref "U6") (pin "5") (pinfunction "SHDN_5") (pintype "input+no_connect"))
    )
  )
)
